# MSP-EXP430F5529LP.net
KiCad netlist of a schematic drawn in EAGLE
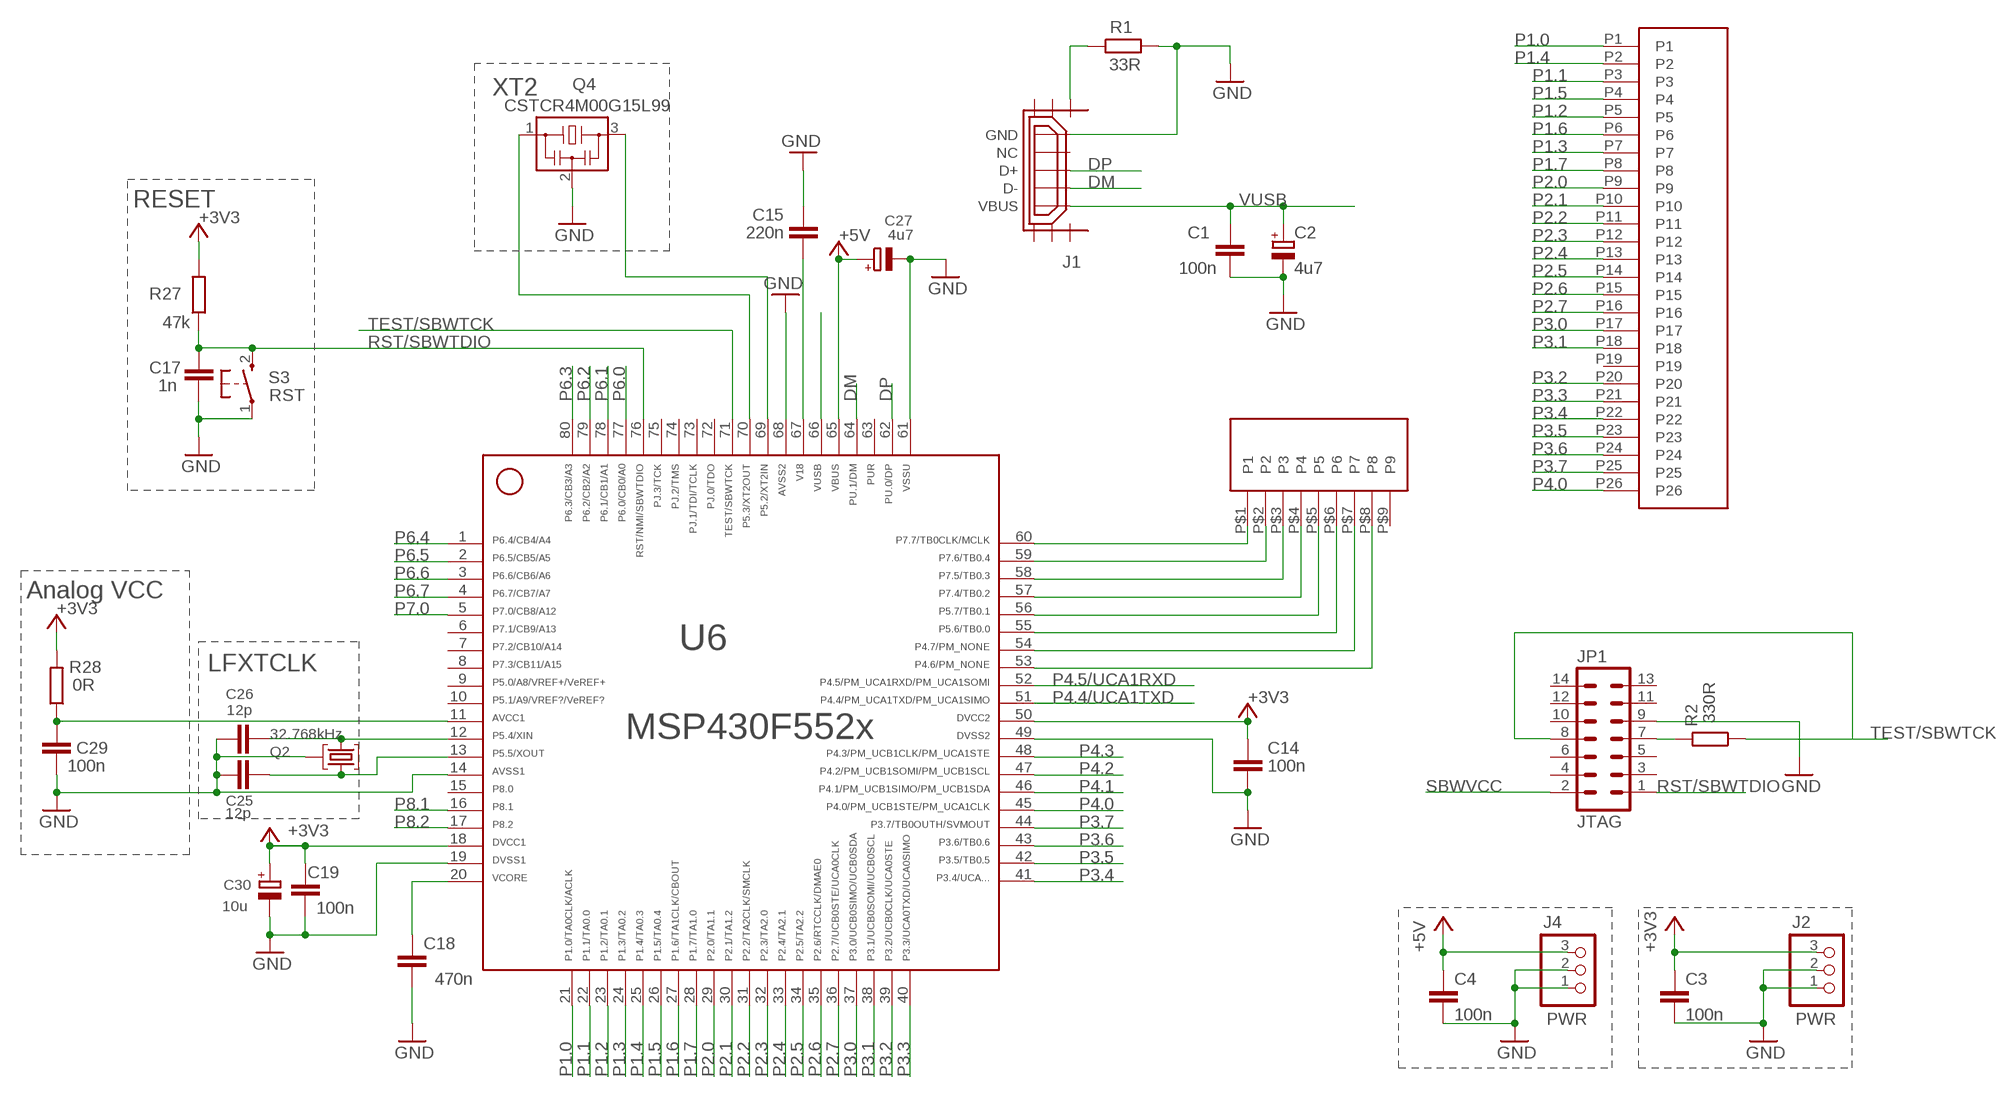
[diagram p0: schematic, sheet 1]

(export (version "E")
  (design (tool "Eeschema 10.0.6"))
  (components
    (comp (ref "C1")
      (value "100n")
      (footprint "eagle-import:C0402")
      (libsource (lib "eagle-import") (part "C-EUC0402"))
    )
    (comp (ref "C2")
      (value "4u7")
      (footprint "eagle-import:A_3216-18R")
      (libsource (lib "eagle-import") (part "CPOL-EUA/3216-18R"))
    )
    (comp (ref "C3")
      (value "100n")
      (footprint "eagle-import:C0402")
      (libsource (lib "eagle-import") (part "C-EUC0402"))
    )
    (comp (ref "C4")
      (value "100n")
      (footprint "eagle-import:C0402")
      (libsource (lib "eagle-import") (part "C-EUC0402"))
    )
    (comp (ref "C14")
      (value "100n")
      (footprint "eagle-import:C0402")
      (libsource (lib "eagle-import") (part "C-EUC0402"))
    )
    (comp (ref "C15")
      (value "220n")
      (footprint "eagle-import:C0402")
      (libsource (lib "eagle-import") (part "C-EUC0402"))
    )
    (comp (ref "C17")
      (value "1n")
      (footprint "eagle-import:C0402")
      (libsource (lib "eagle-import") (part "C-EUC0402"))
    )
    (comp (ref "C18")
      (value "470n")
      (footprint "eagle-import:C0402")
      (libsource (lib "eagle-import") (part "C-EUC0402"))
    )
    (comp (ref "C19")
      (value "100n")
      (footprint "eagle-import:C0402")
      (libsource (lib "eagle-import") (part "C-EUC0402"))
    )
    (comp (ref "C25")
      (value "12p")
      (footprint "eagle-import:C0402")
      (libsource (lib "eagle-import") (part "C-EUC0402"))
    )
    (comp (ref "C26")
      (value "12p")
      (footprint "eagle-import:C0402")
      (libsource (lib "eagle-import") (part "C-EUC0402"))
    )
    (comp (ref "C27")
      (value "4u7")
      (footprint "eagle-import:A_3216-18R")
      (libsource (lib "eagle-import") (part "CPOL-EUA/3216-18R"))
    )
    (comp (ref "C29")
      (value "100n")
      (footprint "eagle-import:C0402")
      (libsource (lib "eagle-import") (part "C-EUC0402"))
    )
    (comp (ref "C30")
      (value "10u")
      (footprint "eagle-import:A_3216-18R")
      (libsource (lib "eagle-import") (part "CPOL-EUA/3216-18R"))
    )
    (comp (ref "J1")
      (value "USB_MICRO_FLIPPED")
      (footprint "eagle-import:HIROSE-ZX62R-B-5P")
      (libsource (lib "eagle-import") (part "USB_MICRO_FLIPPED"))
    )
    (comp (ref "J2")
      (value "PWR")
      (footprint "eagle-import:1X03")
      (libsource (lib "eagle-import") (part "PINHD-1X3"))
    )
    (comp (ref "J4")
      (value "PWR")
      (footprint "eagle-import:1X03")
      (libsource (lib "eagle-import") (part "PINHD-1X3"))
    )
    (comp (ref "JP1")
      (value "JTAG")
      (footprint "eagle-import:MA07-2")
      (libsource (lib "eagle-import") (part "MA07-2"))
    )
    (comp (ref "Q2")
      (value "32.768kHz")
      (footprint "eagle-import:MS3V-T1R")
      (libsource (lib "eagle-import") (part "MS3V-T1R"))
    )
    (comp (ref "Q4")
      (value "CSTCR4M00G15L99")
      (footprint "eagle-import:MURATA-FILTER_CSTCR")
      (fields (field (name "MPN") "CSTCR6M00G53-R0"))
      (libsource (lib "eagle-import") (part "MURATA-FILTER_CSTCR6M00G53Z"))
    )
    (comp (ref "R1")
      (value "33R")
      (footprint "eagle-import:R0402")
      (libsource (lib "eagle-import") (part "R-EU_R0402"))
    )
    (comp (ref "R2")
      (value "330R")
      (footprint "eagle-import:R0402")
      (libsource (lib "eagle-import") (part "R-EU_R0402"))
    )
    (comp (ref "R27")
      (value "47k")
      (footprint "eagle-import:R0402")
      (libsource (lib "eagle-import") (part "R-EU_R0402"))
    )
    (comp (ref "R28")
      (value "0R")
      (footprint "eagle-import:R0402")
      (libsource (lib "eagle-import") (part "R-EU_R0402"))
    )
    (comp (ref "S3")
      (value "RST")
      (footprint "eagle-import:PBTH")
      (libsource (lib "eagle-import") (part "PB"))
    )
    (comp (ref "U$1")
      (value "52806-0910")
      (footprint "eagle-import:SD-52806-09")
      (libsource (lib "eagle-import") (part "52806-0910"))
    )
    (comp (ref "U$2")
      (value "52808-267126")
      (footprint "eagle-import:SD-52808-025")
      (libsource (lib "eagle-import") (part "52808-267126"))
    )
    (comp (ref "U6")
      (value "MSP430F5529IPNR")
      (footprint "eagle-import:PN80")
      (libsource (lib "eagle-import") (part "F552X---PN80"))
    )
  )
  (nets
    (net (code "1") (name "+3V3") (class "Default")
      (node (ref "C14") (pin "1") (pinfunction "1_1") (pintype "passive"))
      (node (ref "C19") (pin "2") (pinfunction "2_2") (pintype "passive"))
      (node (ref "C3") (pin "1") (pinfunction "1_1") (pintype "passive"))
      (node (ref "C30") (pin "+") (pinfunction "+_+") (pintype "passive"))
      (node (ref "J2") (pin "3") (pinfunction "3_3") (pintype "passive"))
      (node (ref "R27") (pin "2") (pinfunction "2_2") (pintype "passive"))
      (node (ref "R28") (pin "2") (pinfunction "2_2") (pintype "passive"))
      (node (ref "U6") (pin "18") (pinfunction "18_18") (pintype "power_in"))
      (node (ref "U6") (pin "50") (pinfunction "50_50") (pintype "power_in"))
    )
    (net (code "2") (name "+5V") (class "Default")
      (node (ref "C27") (pin "+") (pinfunction "+_+") (pintype "passive"))
      (node (ref "C4") (pin "1") (pinfunction "1_1") (pintype "passive"))
      (node (ref "J4") (pin "3") (pinfunction "3_3") (pintype "passive"))
      (node (ref "U6") (pin "65") (pinfunction "65_65") (pintype "power_in"))
    )
    (net (code "3") (name "/DM") (class "Default")
      (node (ref "J1") (pin "D-") (pinfunction "D-_D-") (pintype "input"))
      (node (ref "U6") (pin "64") (pinfunction "64_64") (pintype "bidirectional"))
    )
    (net (code "4") (name "/DP") (class "Default")
      (node (ref "J1") (pin "D+") (pinfunction "D+_D+") (pintype "input"))
      (node (ref "U6") (pin "62") (pinfunction "62_62") (pintype "bidirectional"))
    )
    (net (code "5") (name "/P1.0") (class "Default")
      (node (ref "U$2") (pin "P1") (pinfunction "P1_P1") (pintype "bidirectional"))
      (node (ref "U6") (pin "21") (pinfunction "21_21") (pintype "bidirectional"))
    )
    (net (code "6") (name "/P1.1") (class "Default")
      (node (ref "U$2") (pin "P3") (pinfunction "P3_P3") (pintype "bidirectional"))
      (node (ref "U6") (pin "22") (pinfunction "22_22") (pintype "bidirectional"))
    )
    (net (code "7") (name "/P1.2") (class "Default")
      (node (ref "U$2") (pin "P5") (pinfunction "P5_P5") (pintype "bidirectional"))
      (node (ref "U6") (pin "23") (pinfunction "23_23") (pintype "bidirectional"))
    )
    (net (code "8") (name "/P1.3") (class "Default")
      (node (ref "U$2") (pin "P7") (pinfunction "P7_P7") (pintype "bidirectional"))
      (node (ref "U6") (pin "24") (pinfunction "24_24") (pintype "bidirectional"))
    )
    (net (code "9") (name "/P1.4") (class "Default")
      (node (ref "U$2") (pin "P2") (pinfunction "P2_P2") (pintype "bidirectional"))
      (node (ref "U6") (pin "25") (pinfunction "25_25") (pintype "bidirectional"))
    )
    (net (code "10") (name "/P1.5") (class "Default")
      (node (ref "U$2") (pin "P4") (pinfunction "P4_P4") (pintype "bidirectional"))
      (node (ref "U6") (pin "26") (pinfunction "26_26") (pintype "bidirectional"))
    )
    (net (code "11") (name "/P1.6") (class "Default")
      (node (ref "U$2") (pin "P6") (pinfunction "P6_P6") (pintype "bidirectional"))
      (node (ref "U6") (pin "27") (pinfunction "27_27") (pintype "bidirectional"))
    )
    (net (code "12") (name "/P1.7") (class "Default")
      (node (ref "U$2") (pin "P8") (pinfunction "P8_P8") (pintype "bidirectional"))
      (node (ref "U6") (pin "28") (pinfunction "28_28") (pintype "bidirectional"))
    )
    (net (code "13") (name "/P2.0") (class "Default")
      (node (ref "U$2") (pin "P9") (pinfunction "P9_P9") (pintype "bidirectional"))
      (node (ref "U6") (pin "29") (pinfunction "29_29") (pintype "bidirectional"))
    )
    (net (code "14") (name "/P2.1") (class "Default")
      (node (ref "U$2") (pin "P10") (pinfunction "P10_P10") (pintype "bidirectional"))
      (node (ref "U6") (pin "30") (pinfunction "30_30") (pintype "bidirectional"))
    )
    (net (code "15") (name "/P2.2") (class "Default")
      (node (ref "U$2") (pin "P11") (pinfunction "P11_P11") (pintype "bidirectional"))
      (node (ref "U6") (pin "31") (pinfunction "31_31") (pintype "bidirectional"))
    )
    (net (code "16") (name "/P2.3") (class "Default")
      (node (ref "U$2") (pin "P12") (pinfunction "P12_P12") (pintype "bidirectional"))
      (node (ref "U6") (pin "32") (pinfunction "32_32") (pintype "bidirectional"))
    )
    (net (code "17") (name "/P2.4") (class "Default")
      (node (ref "U$2") (pin "P13") (pinfunction "P13_P13") (pintype "bidirectional"))
      (node (ref "U6") (pin "33") (pinfunction "33_33") (pintype "bidirectional"))
    )
    (net (code "18") (name "/P2.5") (class "Default")
      (node (ref "U$2") (pin "P14") (pinfunction "P14_P14") (pintype "bidirectional"))
      (node (ref "U6") (pin "34") (pinfunction "34_34") (pintype "bidirectional"))
    )
    (net (code "19") (name "/P2.6") (class "Default")
      (node (ref "U$2") (pin "P15") (pinfunction "P15_P15") (pintype "bidirectional"))
      (node (ref "U6") (pin "35") (pinfunction "35_35") (pintype "bidirectional"))
    )
    (net (code "20") (name "/P2.7") (class "Default")
      (node (ref "U$2") (pin "P16") (pinfunction "P16_P16") (pintype "bidirectional"))
      (node (ref "U6") (pin "36") (pinfunction "36_36") (pintype "bidirectional"))
    )
    (net (code "21") (name "/P3.0") (class "Default")
      (node (ref "U$2") (pin "P17") (pinfunction "P17_P17") (pintype "bidirectional"))
      (node (ref "U6") (pin "37") (pinfunction "37_37") (pintype "bidirectional"))
    )
    (net (code "22") (name "/P3.1") (class "Default")
      (node (ref "U$2") (pin "P18") (pinfunction "P18_P18") (pintype "bidirectional"))
      (node (ref "U6") (pin "38") (pinfunction "38_38") (pintype "bidirectional"))
    )
    (net (code "23") (name "/P3.2") (class "Default")
      (node (ref "U$2") (pin "P20") (pinfunction "P20_P20") (pintype "bidirectional"))
      (node (ref "U6") (pin "39") (pinfunction "39_39") (pintype "bidirectional"))
    )
    (net (code "24") (name "/P3.3") (class "Default")
      (node (ref "U$2") (pin "P21") (pinfunction "P21_P21") (pintype "bidirectional"))
      (node (ref "U6") (pin "40") (pinfunction "40_40") (pintype "bidirectional"))
    )
    (net (code "25") (name "/P3.4") (class "Default")
      (node (ref "U$2") (pin "P22") (pinfunction "P22_P22") (pintype "bidirectional"))
      (node (ref "U6") (pin "41") (pinfunction "41_41") (pintype "bidirectional"))
    )
    (net (code "26") (name "/P3.5") (class "Default")
      (node (ref "U$2") (pin "P23") (pinfunction "P23_P23") (pintype "bidirectional"))
      (node (ref "U6") (pin "42") (pinfunction "42_42") (pintype "bidirectional"))
    )
    (net (code "27") (name "/P3.6") (class "Default")
      (node (ref "U$2") (pin "P24") (pinfunction "P24_P24") (pintype "bidirectional"))
      (node (ref "U6") (pin "43") (pinfunction "43_43") (pintype "bidirectional"))
    )
    (net (code "28") (name "/P3.7") (class "Default")
      (node (ref "U$2") (pin "P25") (pinfunction "P25_P25") (pintype "bidirectional"))
      (node (ref "U6") (pin "44") (pinfunction "44_44") (pintype "bidirectional"))
    )
    (net (code "29") (name "/P4.0") (class "Default")
      (node (ref "U$2") (pin "P26") (pinfunction "P26_P26") (pintype "bidirectional"))
      (node (ref "U6") (pin "45") (pinfunction "45_45") (pintype "bidirectional"))
    )
    (net (code "30") (name "/P4.1") (class "Default")
      (node (ref "U6") (pin "46") (pinfunction "46_46") (pintype "bidirectional"))
    )
    (net (code "31") (name "/P4.2") (class "Default")
      (node (ref "U6") (pin "47") (pinfunction "47_47") (pintype "bidirectional"))
    )
    (net (code "32") (name "/P4.3") (class "Default")
      (node (ref "U6") (pin "48") (pinfunction "48_48") (pintype "bidirectional"))
    )
    (net (code "33") (name "/P4.4{slash}UCA1TXD") (class "Default")
      (node (ref "U6") (pin "51") (pinfunction "51_51") (pintype "bidirectional"))
    )
    (net (code "34") (name "/P4.5{slash}UCA1RXD") (class "Default")
      (node (ref "U6") (pin "52") (pinfunction "52_52") (pintype "bidirectional"))
    )
    (net (code "35") (name "/P6.0") (class "Default")
      (node (ref "U6") (pin "77") (pinfunction "77_77") (pintype "bidirectional"))
    )
    (net (code "36") (name "/P6.1") (class "Default")
      (node (ref "U6") (pin "78") (pinfunction "78_78") (pintype "bidirectional"))
    )
    (net (code "37") (name "/P6.2") (class "Default")
      (node (ref "U6") (pin "79") (pinfunction "79_79") (pintype "bidirectional"))
    )
    (net (code "38") (name "/P6.3") (class "Default")
      (node (ref "U6") (pin "80") (pinfunction "80_80") (pintype "bidirectional"))
    )
    (net (code "39") (name "/P6.4") (class "Default")
      (node (ref "U6") (pin "1") (pinfunction "1_1") (pintype "bidirectional"))
    )
    (net (code "40") (name "/P6.5") (class "Default")
      (node (ref "U6") (pin "2") (pinfunction "2_2") (pintype "bidirectional"))
    )
    (net (code "41") (name "/P6.6") (class "Default")
      (node (ref "U6") (pin "3") (pinfunction "3_3") (pintype "bidirectional"))
    )
    (net (code "42") (name "/P6.7") (class "Default")
      (node (ref "U6") (pin "4") (pinfunction "4_4") (pintype "bidirectional"))
    )
    (net (code "43") (name "/P7.0") (class "Default")
      (node (ref "U6") (pin "5") (pinfunction "5_5") (pintype "bidirectional"))
    )
    (net (code "44") (name "/P8.1") (class "Default")
      (node (ref "U6") (pin "16") (pinfunction "16_16") (pintype "bidirectional"))
    )
    (net (code "45") (name "/P8.2") (class "Default")
      (node (ref "U6") (pin "17") (pinfunction "17_17") (pintype "bidirectional"))
    )
    (net (code "46") (name "/RST{slash}SBWTDIO") (class "Default")
      (node (ref "C17") (pin "1") (pinfunction "1_1") (pintype "passive"))
      (node (ref "JP1") (pin "1") (pinfunction "1_1") (pintype "passive"))
      (node (ref "R27") (pin "1") (pinfunction "1_1") (pintype "passive"))
      (node (ref "S3") (pin "2") (pinfunction "S_2") (pintype "passive"))
      (node (ref "U6") (pin "76") (pinfunction "76_76") (pintype "bidirectional"))
    )
    (net (code "47") (name "/SBWVCC") (class "Default")
      (node (ref "JP1") (pin "2") (pinfunction "2_2") (pintype "passive"))
    )
    (net (code "48") (name "/TEST{slash}SBWTCK") (class "Default")
      (node (ref "JP1") (pin "8") (pinfunction "8_8") (pintype "passive"))
      (node (ref "R2") (pin "1") (pinfunction "1_1") (pintype "passive"))
      (node (ref "U6") (pin "71") (pinfunction "71_71") (pintype "input"))
    )
    (net (code "49") (name "/VUSB") (class "Default")
      (node (ref "C1") (pin "1") (pinfunction "1_1") (pintype "passive"))
      (node (ref "C2") (pin "+") (pinfunction "+_+") (pintype "passive"))
      (node (ref "J1") (pin "VBUS") (pinfunction "VBUS_VBUS") (pintype "input"))
      (node (ref "U6") (pin "66") (pinfunction "66_66") (pintype "power_in"))
    )
    (net (code "50") (name "GND") (class "Default")
      (node (ref "C1") (pin "2") (pinfunction "2_2") (pintype "passive"))
      (node (ref "C14") (pin "2") (pinfunction "2_2") (pintype "passive"))
      (node (ref "C15") (pin "2") (pinfunction "2_2") (pintype "passive"))
      (node (ref "C17") (pin "2") (pinfunction "2_2") (pintype "passive"))
      (node (ref "C18") (pin "1") (pinfunction "1_1") (pintype "passive"))
      (node (ref "C19") (pin "1") (pinfunction "1_1") (pintype "passive"))
      (node (ref "C2") (pin "-") (pinfunction "-_-") (pintype "passive"))
      (node (ref "C25") (pin "1") (pinfunction "1_1") (pintype "passive"))
      (node (ref "C26") (pin "1") (pinfunction "1_1") (pintype "passive"))
      (node (ref "C27") (pin "-") (pinfunction "-_-") (pintype "passive"))
      (node (ref "C29") (pin "2") (pinfunction "2_2") (pintype "passive"))
      (node (ref "C3") (pin "2") (pinfunction "2_2") (pintype "passive"))
      (node (ref "C30") (pin "-") (pinfunction "-_-") (pintype "passive"))
      (node (ref "C4") (pin "2") (pinfunction "2_2") (pintype "passive"))
      (node (ref "J1") (pin "GND") (pinfunction "GND_GND") (pintype "input"))
      (node (ref "J2") (pin "1") (pinfunction "1_1") (pintype "passive"))
      (node (ref "J2") (pin "2") (pinfunction "2_2") (pintype "passive"))
      (node (ref "J4") (pin "1") (pinfunction "1_1") (pintype "passive"))
      (node (ref "J4") (pin "2") (pinfunction "2_2") (pintype "passive"))
      (node (ref "JP1") (pin "9") (pinfunction "9_9") (pintype "passive"))
      (node (ref "Q2") (pin "P3") (pinfunction "GND_P3") (pintype "power_in"))
      (node (ref "Q4") (pin "2") (pinfunction "2_2") (pintype "passive"))
      (node (ref "R1") (pin "2") (pinfunction "2_2") (pintype "passive"))
      (node (ref "S3") (pin "1") (pinfunction "P_1") (pintype "passive"))
      (node (ref "U6") (pin "14") (pinfunction "14_14") (pintype "power_in"))
      (node (ref "U6") (pin "19") (pinfunction "19_19") (pintype "power_in"))
      (node (ref "U6") (pin "49") (pinfunction "49_49") (pintype "power_in"))
      (node (ref "U6") (pin "61") (pinfunction "61_61") (pintype "power_in"))
      (node (ref "U6") (pin "68") (pinfunction "68_68") (pintype "power_in"))
    )
    (net (code "51") (name "Net-(C15-Pad1)") (class "Default")
      (node (ref "C15") (pin "1") (pinfunction "1_1") (pintype "passive"))
      (node (ref "U6") (pin "67") (pinfunction "67_67") (pintype "power_in"))
    )
    (net (code "52") (name "Net-(C18-Pad2)") (class "Default")
      (node (ref "C18") (pin "2") (pinfunction "2_2") (pintype "passive"))
      (node (ref "U6") (pin "20") (pinfunction "20_20") (pintype "power_in"))
    )
    (net (code "53") (name "Net-(C29-Pad1)") (class "Default")
      (node (ref "C29") (pin "1") (pinfunction "1_1") (pintype "passive"))
      (node (ref "R28") (pin "1") (pinfunction "1_1") (pintype "passive"))
      (node (ref "U6") (pin "11") (pinfunction "11_11") (pintype "power_in"))
    )
    (net (code "54") (name "Net-(J1-PadSHIELD1)") (class "Default")
      (node (ref "J1") (pin "SHIELD1") (pinfunction "SHIELD1_SHIELD1") (pintype "bidirectional"))
      (node (ref "R1") (pin "1") (pinfunction "1_1") (pintype "passive"))
    )
    (net (code "55") (name "Net-(JP1-Pad7)") (class "Default")
      (node (ref "JP1") (pin "7") (pinfunction "7_7") (pintype "passive"))
      (node (ref "R2") (pin "2") (pinfunction "2_2") (pintype "passive"))
    )
    (net (code "56") (name "Net-(Q2-1)") (class "Default")
      (node (ref "C25") (pin "2") (pinfunction "2_2") (pintype "passive"))
      (node (ref "Q2") (pin "P1") (pinfunction "1_P1") (pintype "bidirectional"))
      (node (ref "U6") (pin "13") (pinfunction "13_13") (pintype "bidirectional"))
    )
    (net (code "57") (name "Net-(Q2-2)") (class "Default")
      (node (ref "C26") (pin "2") (pinfunction "2_2") (pintype "passive"))
      (node (ref "Q2") (pin "P2") (pinfunction "2_P2") (pintype "bidirectional"))
      (node (ref "U6") (pin "12") (pinfunction "12_12") (pintype "bidirectional"))
    )
    (net (code "58") (name "Net-(Q4-Pad1)") (class "Default")
      (node (ref "Q4") (pin "1") (pinfunction "1_1") (pintype "passive"))
      (node (ref "U6") (pin "70") (pinfunction "70_70") (pintype "bidirectional"))
    )
    (net (code "59") (name "Net-(Q4-Pad3)") (class "Default")
      (node (ref "Q4") (pin "3") (pinfunction "3_3") (pintype "passive"))
      (node (ref "U6") (pin "69") (pinfunction "69_69") (pintype "bidirectional"))
    )
    (net (code "60") (name "Net-(U$1-P1)") (class "Default")
      (node (ref "U$1") (pin "P$1") (pinfunction "P1_P$1") (pintype "bidirectional"))
      (node (ref "U6") (pin "60") (pinfunction "60_60") (pintype "bidirectional"))
    )
    (net (code "61") (name "Net-(U$1-P2)") (class "Default")
      (node (ref "U$1") (pin "P$2") (pinfunction "P2_P$2") (pintype "bidirectional"))
      (node (ref "U6") (pin "59") (pinfunction "59_59") (pintype "bidirectional"))
    )
    (net (code "62") (name "Net-(U$1-P3)") (class "Default")
      (node (ref "U$1") (pin "P$3") (pinfunction "P3_P$3") (pintype "bidirectional"))
      (node (ref "U6") (pin "58") (pinfunction "58_58") (pintype "bidirectional"))
    )
    (net (code "63") (name "Net-(U$1-P4)") (class "Default")
      (node (ref "U$1") (pin "P$4") (pinfunction "P4_P$4") (pintype "bidirectional"))
      (node (ref "U6") (pin "57") (pinfunction "57_57") (pintype "bidirectional"))
    )
    (net (code "64") (name "Net-(U$1-P5)") (class "Default")
      (node (ref "U$1") (pin "P$5") (pinfunction "P5_P$5") (pintype "bidirectional"))
      (node (ref "U6") (pin "56") (pinfunction "56_56") (pintype "bidirectional"))
    )
    (net (code "65") (name "Net-(U$1-P6)") (class "Default")
      (node (ref "U$1") (pin "P$6") (pinfunction "P6_P$6") (pintype "bidirectional"))
      (node (ref "U6") (pin "55") (pinfunction "55_55") (pintype "bidirectional"))
    )
    (net (code "66") (name "Net-(U$1-P7)") (class "Default")
      (node (ref "U$1") (pin "P$7") (pinfunction "P7_P$7") (pintype "bidirectional"))
      (node (ref "U6") (pin "54") (pinfunction "54_54") (pintype "bidirectional"))
    )
    (net (code "67") (name "Net-(U$1-P8)") (class "Default")
      (node (ref "U$1") (pin "P$8") (pinfunction "P8_P$8") (pintype "bidirectional"))
      (node (ref "U6") (pin "53") (pinfunction "53_53") (pintype "bidirectional"))
    )
    (net (code "68") (name "unconnected-(J1-PadNC)") (class "Default")
      (node (ref "J1") (pin "NC") (pinfunction "NC_NC") (pintype "input"))
    )
    (net (code "69") (name "unconnected-(J1-PadSHIELD2)") (class "Default")
      (node (ref "J1") (pin "SHIELD2") (pinfunction "SHIELD2_SHIELD2") (pintype "bidirectional"))
    )
    (net (code "70") (name "unconnected-(J1-PadSHIELD3)") (class "Default")
      (node (ref "J1") (pin "SHIELD3") (pinfunction "SHIELD3_SHIELD3") (pintype "bidirectional"))
    )
    (net (code "71") (name "unconnected-(J1-PadSHIELD4)") (class "Default")
      (node (ref "J1") (pin "SHIELD4") (pinfunction "SHIELD4_SHIELD4") (pintype "bidirectional"))
    )
    (net (code "72") (name "unconnected-(J1-PadSHIELD5)") (class "Default")
      (node (ref "J1") (pin "SHIELD5") (pinfunction "SHIELD5_SHIELD5") (pintype "bidirectional"))
    )
    (net (code "73") (name "unconnected-(J1-PadSHIELD6)") (class "Default")
      (node (ref "J1") (pin "SHIELD6") (pinfunction "SHIELD6_SHIELD6") (pintype "bidirectional"))
    )
    (net (code "74") (name "unconnected-(JP1-Pad3)") (class "Default")
      (node (ref "JP1") (pin "3") (pinfunction "3_3") (pintype "passive"))
    )
    (net (code "75") (name "unconnected-(JP1-Pad4)") (class "Default")
      (node (ref "JP1") (pin "4") (pinfunction "4_4") (pintype "passive"))
    )
    (net (code "76") (name "unconnected-(JP1-Pad5)") (class "Default")
      (node (ref "JP1") (pin "5") (pinfunction "5_5") (pintype "passive"))
    )
    (net (code "77") (name "unconnected-(JP1-Pad6)") (class "Default")
      (node (ref "JP1") (pin "6") (pinfunction "6_6") (pintype "passive"))
    )
    (net (code "78") (name "unconnected-(JP1-Pad10)") (class "Default")
      (node (ref "JP1") (pin "10") (pinfunction "10_10") (pintype "passive"))
    )
    (net (code "79") (name "unconnected-(JP1-Pad11)") (class "Default")
      (node (ref "JP1") (pin "11") (pinfunction "11_11") (pintype "passive"))
    )
    (net (code "80") (name "unconnected-(JP1-Pad12)") (class "Default")
      (node (ref "JP1") (pin "12") (pinfunction "12_12") (pintype "passive"))
    )
    (net (code "81") (name "unconnected-(JP1-Pad13)") (class "Default")
      (node (ref "JP1") (pin "13") (pinfunction "13_13") (pintype "passive"))
    )
    (net (code "82") (name "unconnected-(JP1-Pad14)") (class "Default")
      (node (ref "JP1") (pin "14") (pinfunction "14_14") (pintype "passive"))
    )
    (net (code "83") (name "unconnected-(U$1-P9-PadP$9)") (class "Default")
      (node (ref "U$1") (pin "P$9") (pinfunction "P9_P$9") (pintype "bidirectional"))
    )
    (net (code "84") (name "unconnected-(U$2-PadP19)") (class "Default")
      (node (ref "U$2") (pin "P19") (pinfunction "P19_P19") (pintype "bidirectional"))
    )
    (net (code "85") (name "unconnected-(U6-Pad6)") (class "Default")
      (node (ref "U6") (pin "6") (pinfunction "6_6") (pintype "bidirectional"))
    )
    (net (code "86") (name "unconnected-(U6-Pad7)") (class "Default")
      (node (ref "U6") (pin "7") (pinfunction "7_7") (pintype "bidirectional"))
    )
    (net (code "87") (name "unconnected-(U6-Pad8)") (class "Default")
      (node (ref "U6") (pin "8") (pinfunction "8_8") (pintype "bidirectional"))
    )
    (net (code "88") (name "unconnected-(U6-Pad9)") (class "Default")
      (node (ref "U6") (pin "9") (pinfunction "9_9") (pintype "bidirectional"))
    )
    (net (code "89") (name "unconnected-(U6-Pad10)") (class "Default")
      (node (ref "U6") (pin "10") (pinfunction "10_10") (pintype "bidirectional"))
    )
    (net (code "90") (name "unconnected-(U6-Pad15)") (class "Default")
      (node (ref "U6") (pin "15") (pinfunction "15_15") (pintype "bidirectional"))
    )
    (net (code "91") (name "unconnected-(U6-Pad63)") (class "Default")
      (node (ref "U6") (pin "63") (pinfunction "63_63") (pintype "bidirectional"))
    )
    (net (code "92") (name "unconnected-(U6-Pad72)") (class "Default")
      (node (ref "U6") (pin "72") (pinfunction "72_72") (pintype "bidirectional"))
    )
    (net (code "93") (name "unconnected-(U6-Pad73)") (class "Default")
      (node (ref "U6") (pin "73") (pinfunction "73_73") (pintype "bidirectional"))
    )
    (net (code "94") (name "unconnected-(U6-Pad74)") (class "Default")
      (node (ref "U6") (pin "74") (pinfunction "74_74") (pintype "bidirectional"))
    )
    (net (code "95") (name "unconnected-(U6-Pad75)") (class "Default")
      (node (ref "U6") (pin "75") (pinfunction "75_75") (pintype "bidirectional"))
    )
  )
)
